# ICEBoard.net
KiCad netlist of a schematic drawn in Altium Designer
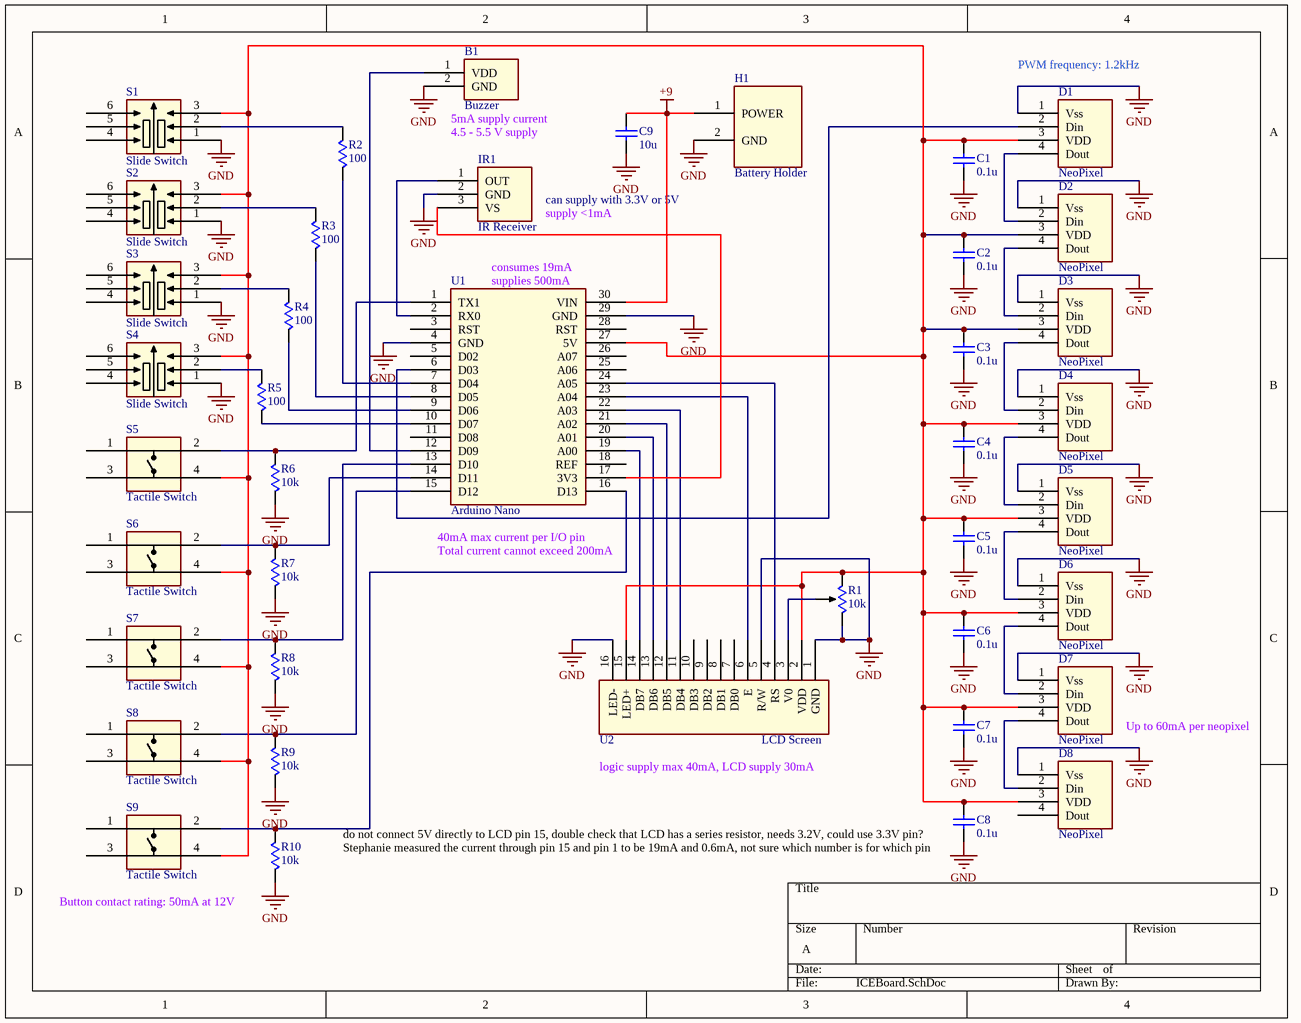
[diagram p0: ICEBoard.SchDoc]

(export (version "E")
  (design (tool "Eeschema 10.0.6"))
  (components
    (comp (ref "B1") (value "Buzzer") (footprint "TP124005") (libsource (lib "TP124005") (part "TP124005")))
    (comp (ref "C1") (value "0.1u") (footprint "Capacitor") (libsource (lib "Capacitor") (part "Capacitor")))
    (comp (ref "C2") (value "0.1u") (footprint "Capacitor") (libsource (lib "Capacitor") (part "Capacitor")))
    (comp (ref "C3") (value "0.1u") (footprint "Capacitor") (libsource (lib "Capacitor") (part "Capacitor")))
    (comp (ref "C4") (value "0.1u") (footprint "Capacitor") (libsource (lib "Capacitor") (part "Capacitor")))
    (comp (ref "C5") (value "0.1u") (footprint "Capacitor") (libsource (lib "Capacitor") (part "Capacitor")))
    (comp (ref "C6") (value "0.1u") (footprint "Capacitor") (libsource (lib "Capacitor") (part "Capacitor")))
    (comp (ref "C7") (value "0.1u") (footprint "Capacitor") (libsource (lib "Capacitor") (part "Capacitor")))
    (comp (ref "C8") (value "0.1u") (footprint "Capacitor") (libsource (lib "Capacitor") (part "Capacitor")))
    (comp (ref "C9")
      (value "10u")
      (footprint "PCBComponent_1")
      (libsource (lib "Capacitor") (part "Capacitor"))
    )
    (comp (ref "D1") (value "NeoPixel") (footprint "NeoPixel") (libsource (lib "NeoPixel") (part "NeoPixel")))
    (comp (ref "D2") (value "NeoPixel") (footprint "NeoPixel") (libsource (lib "NeoPixel") (part "NeoPixel")))
    (comp (ref "D3") (value "NeoPixel") (footprint "NeoPixel") (libsource (lib "NeoPixel") (part "NeoPixel")))
    (comp (ref "D4") (value "NeoPixel") (footprint "NeoPixel") (libsource (lib "NeoPixel") (part "NeoPixel")))
    (comp (ref "D5") (value "NeoPixel") (footprint "NeoPixel") (libsource (lib "NeoPixel") (part "NeoPixel")))
    (comp (ref "D6") (value "NeoPixel") (footprint "NeoPixel") (libsource (lib "NeoPixel") (part "NeoPixel")))
    (comp (ref "D7") (value "NeoPixel") (footprint "NeoPixel") (libsource (lib "NeoPixel") (part "NeoPixel")))
    (comp (ref "D8") (value "NeoPixel") (footprint "NeoPixel") (libsource (lib "NeoPixel") (part "NeoPixel")))
    (comp (ref "H1") (value "Battery Holder") (footprint "BH9VPC") (libsource (lib "BH9VPC") (part "BH9VPC")))
    (comp (ref "IR1")
      (value "IR Receiver")
      (footprint "TSOP382")
      (libsource (lib "TSOP382") (part "TSOP382"))
    )
    (comp (ref "R1")
      (value "10k")
      (footprint "TC33X")
      (libsource (lib "Resistor - Variable") (part "Resistor - Variable"))
    )
    (comp (ref "R2") (value "100") (footprint "Resistor1608") (libsource (lib "Resistor") (part "Resistor")))
    (comp (ref "R3") (value "100") (footprint "Resistor1608") (libsource (lib "Resistor") (part "Resistor")))
    (comp (ref "R4") (value "100") (footprint "Resistor1608") (libsource (lib "Resistor") (part "Resistor")))
    (comp (ref "R5") (value "100") (footprint "Resistor1608") (libsource (lib "Resistor") (part "Resistor")))
    (comp (ref "R6") (value "10k") (footprint "Resistor1608") (libsource (lib "Resistor") (part "Resistor")))
    (comp (ref "R7") (value "10k") (footprint "Resistor1608") (libsource (lib "Resistor") (part "Resistor")))
    (comp (ref "R8") (value "10k") (footprint "Resistor1608") (libsource (lib "Resistor") (part "Resistor")))
    (comp (ref "R9") (value "10k") (footprint "Resistor1608") (libsource (lib "Resistor") (part "Resistor")))
    (comp (ref "R10") (value "10k") (footprint "Resistor1608") (libsource (lib "Resistor") (part "Resistor")))
    (comp (ref "S1")
      (value "Slide Switch")
      (footprint "JS202011SCQN")
      (libsource (lib "JS202011SCQN") (part "JS202011SCQN"))
    )
    (comp (ref "S2")
      (value "Slide Switch")
      (footprint "JS202011SCQN")
      (libsource (lib "JS202011SCQN") (part "JS202011SCQN"))
    )
    (comp (ref "S3")
      (value "Slide Switch")
      (footprint "JS202011SCQN")
      (libsource (lib "JS202011SCQN") (part "JS202011SCQN"))
    )
    (comp (ref "S4")
      (value "Slide Switch")
      (footprint "JS202011SCQN")
      (libsource (lib "JS202011SCQN") (part "JS202011SCQN"))
    )
    (comp (ref "S5") (value "Tactile Switch") (footprint "PTS645") (libsource (lib "PTS645") (part "PTS645")))
    (comp (ref "S6") (value "Tactile Switch") (footprint "PTS645") (libsource (lib "PTS645") (part "PTS645")))
    (comp (ref "S7") (value "Tactile Switch") (footprint "PTS645") (libsource (lib "PTS645") (part "PTS645")))
    (comp (ref "S8") (value "Tactile Switch") (footprint "PTS645") (libsource (lib "PTS645") (part "PTS645")))
    (comp (ref "S9") (value "Tactile Switch") (footprint "PTS645") (libsource (lib "PTS645") (part "PTS645")))
    (comp (ref "U1")
      (value "Arduino Nano")
      (footprint "ArduinoNano")
      (libsource (lib "ArduinoNano") (part "ArduinoNano"))
    )
    (comp (ref "U2")
      (value "LCD Screen")
      (footprint "TC1602A-01T")
      (libsource (lib "TC1602A-01T") (part "TC1602A-01T"))
    )
  )
  (nets
    (net (code "1") (name "+9") (class "Default")
      (node (ref "C9") (pin "1") (pinfunction "1_1") (pintype "passive"))
      (node (ref "H1") (pin "1") (pinfunction "POWER_1") (pintype "passive"))
      (node (ref "U1") (pin "30") (pinfunction "VIN_30") (pintype "passive"))
    )
    (net (code "2") (name "GND") (class "Default")
      (node (ref "B1") (pin "2") (pinfunction "GND_2") (pintype "passive"))
      (node (ref "C1") (pin "2") (pinfunction "2_2") (pintype "passive"))
      (node (ref "C2") (pin "2") (pinfunction "2_2") (pintype "passive"))
      (node (ref "C3") (pin "2") (pinfunction "2_2") (pintype "passive"))
      (node (ref "C4") (pin "2") (pinfunction "2_2") (pintype "passive"))
      (node (ref "C5") (pin "2") (pinfunction "2_2") (pintype "passive"))
      (node (ref "C6") (pin "2") (pinfunction "2_2") (pintype "passive"))
      (node (ref "C7") (pin "2") (pinfunction "2_2") (pintype "passive"))
      (node (ref "C8") (pin "2") (pinfunction "2_2") (pintype "passive"))
      (node (ref "C9") (pin "2") (pinfunction "2_2") (pintype "passive"))
      (node (ref "D1") (pin "1") (pinfunction "Vss_1") (pintype "passive"))
      (node (ref "D2") (pin "1") (pinfunction "Vss_1") (pintype "passive"))
      (node (ref "D3") (pin "1") (pinfunction "Vss_1") (pintype "passive"))
      (node (ref "D4") (pin "1") (pinfunction "Vss_1") (pintype "passive"))
      (node (ref "D5") (pin "1") (pinfunction "Vss_1") (pintype "passive"))
      (node (ref "D6") (pin "1") (pinfunction "Vss_1") (pintype "passive"))
      (node (ref "D7") (pin "1") (pinfunction "Vss_1") (pintype "passive"))
      (node (ref "D8") (pin "1") (pinfunction "Vss_1") (pintype "passive"))
      (node (ref "H1") (pin "2") (pinfunction "GND_2") (pintype "passive"))
      (node (ref "IR1") (pin "2") (pinfunction "GND_2") (pintype "passive"))
      (node (ref "R1") (pin "1") (pinfunction "1_1") (pintype "passive"))
      (node (ref "R10") (pin "1") (pinfunction "1_1") (pintype "passive"))
      (node (ref "R6") (pin "1") (pinfunction "1_1") (pintype "passive"))
      (node (ref "R7") (pin "1") (pinfunction "1_1") (pintype "passive"))
      (node (ref "R8") (pin "1") (pinfunction "1_1") (pintype "passive"))
      (node (ref "R9") (pin "1") (pinfunction "1_1") (pintype "passive"))
      (node (ref "S1") (pin "1") (pintype "passive"))
      (node (ref "S2") (pin "1") (pintype "passive"))
      (node (ref "S3") (pin "1") (pintype "passive"))
      (node (ref "S4") (pin "1") (pintype "passive"))
      (node (ref "U1") (pin "29") (pinfunction "GND_29") (pintype "passive"))
      (node (ref "U1") (pin "4") (pinfunction "GND_4") (pintype "passive"))
      (node (ref "U2") (pin "1") (pinfunction "GND_1") (pintype "passive"))
      (node (ref "U2") (pin "16") (pinfunction "LED-_16") (pintype "passive"))
      (node (ref "U2") (pin "5") (pinfunction "R/W_5") (pintype "passive"))
    )
    (net (code "3") (name "Net-(B1-VDD)") (class "Default")
      (node (ref "B1") (pin "1") (pinfunction "VDD_1") (pintype "passive"))
      (node (ref "U1") (pin "12") (pinfunction "D09_12") (pintype "passive"))
    )
    (net (code "4") (name "Net-(D1-Din)") (class "Default")
      (node (ref "D1") (pin "2") (pinfunction "Din_2") (pintype "passive"))
      (node (ref "U1") (pin "6") (pinfunction "D03_6") (pintype "passive"))
    )
    (net (code "5") (name "Net-(D1-Dout)") (class "Default")
      (node (ref "D1") (pin "4") (pinfunction "Dout_4") (pintype "passive"))
      (node (ref "D2") (pin "2") (pinfunction "Din_2") (pintype "passive"))
    )
    (net (code "6") (name "Net-(D1-VDD)") (class "Default")
      (node (ref "C1") (pin "1") (pinfunction "1_1") (pintype "passive"))
      (node (ref "C2") (pin "1") (pinfunction "1_1") (pintype "passive"))
      (node (ref "C3") (pin "1") (pinfunction "1_1") (pintype "passive"))
      (node (ref "C4") (pin "1") (pinfunction "1_1") (pintype "passive"))
      (node (ref "C5") (pin "1") (pinfunction "1_1") (pintype "passive"))
      (node (ref "C6") (pin "1") (pinfunction "1_1") (pintype "passive"))
      (node (ref "C7") (pin "1") (pinfunction "1_1") (pintype "passive"))
      (node (ref "C8") (pin "1") (pinfunction "1_1") (pintype "passive"))
      (node (ref "D1") (pin "3") (pinfunction "VDD_3") (pintype "passive"))
      (node (ref "D2") (pin "3") (pinfunction "VDD_3") (pintype "passive"))
      (node (ref "D3") (pin "3") (pinfunction "VDD_3") (pintype "passive"))
      (node (ref "D4") (pin "3") (pinfunction "VDD_3") (pintype "passive"))
      (node (ref "D5") (pin "3") (pinfunction "VDD_3") (pintype "passive"))
      (node (ref "D6") (pin "3") (pinfunction "VDD_3") (pintype "passive"))
      (node (ref "D7") (pin "3") (pinfunction "VDD_3") (pintype "passive"))
      (node (ref "D8") (pin "3") (pinfunction "VDD_3") (pintype "passive"))
      (node (ref "R1") (pin "3") (pinfunction "3_3") (pintype "passive"))
      (node (ref "S1") (pin "3") (pintype "passive"))
      (node (ref "S2") (pin "3") (pintype "passive"))
      (node (ref "S3") (pin "3") (pintype "passive"))
      (node (ref "S4") (pin "3") (pintype "passive"))
      (node (ref "S5") (pin "4") (pintype "passive"))
      (node (ref "S6") (pin "4") (pintype "passive"))
      (node (ref "S7") (pin "4") (pintype "passive"))
      (node (ref "S8") (pin "4") (pintype "passive"))
      (node (ref "S9") (pin "4") (pintype "passive"))
      (node (ref "U1") (pin "27") (pinfunction "5V_27") (pintype "passive"))
      (node (ref "U2") (pin "15") (pinfunction "LED+_15") (pintype "passive"))
      (node (ref "U2") (pin "2") (pinfunction "VDD_2") (pintype "passive"))
    )
    (net (code "7") (name "Net-(D2-Dout)") (class "Default")
      (node (ref "D2") (pin "4") (pinfunction "Dout_4") (pintype "passive"))
      (node (ref "D3") (pin "2") (pinfunction "Din_2") (pintype "passive"))
    )
    (net (code "8") (name "Net-(D3-Dout)") (class "Default")
      (node (ref "D3") (pin "4") (pinfunction "Dout_4") (pintype "passive"))
      (node (ref "D4") (pin "2") (pinfunction "Din_2") (pintype "passive"))
    )
    (net (code "9") (name "Net-(D4-Dout)") (class "Default")
      (node (ref "D4") (pin "4") (pinfunction "Dout_4") (pintype "passive"))
      (node (ref "D5") (pin "2") (pinfunction "Din_2") (pintype "passive"))
    )
    (net (code "10") (name "Net-(D5-Dout)") (class "Default")
      (node (ref "D5") (pin "4") (pinfunction "Dout_4") (pintype "passive"))
      (node (ref "D6") (pin "2") (pinfunction "Din_2") (pintype "passive"))
    )
    (net (code "11") (name "Net-(D6-Dout)") (class "Default")
      (node (ref "D6") (pin "4") (pinfunction "Dout_4") (pintype "passive"))
      (node (ref "D7") (pin "2") (pinfunction "Din_2") (pintype "passive"))
    )
    (net (code "12") (name "Net-(D7-Dout)") (class "Default")
      (node (ref "D7") (pin "4") (pinfunction "Dout_4") (pintype "passive"))
      (node (ref "D8") (pin "2") (pinfunction "Din_2") (pintype "passive"))
    )
    (net (code "13") (name "Net-(IR1-OUT)") (class "Default")
      (node (ref "IR1") (pin "1") (pinfunction "OUT_1") (pintype "passive"))
      (node (ref "U1") (pin "2") (pinfunction "RX0_2") (pintype "passive"))
    )
    (net (code "14") (name "Net-(IR1-VS)") (class "Default")
      (node (ref "IR1") (pin "3") (pinfunction "VS_3") (pintype "passive"))
      (node (ref "U1") (pin "17") (pinfunction "3V3_17") (pintype "passive"))
    )
    (net (code "15") (name "Net-(R2-Pad2)") (class "Default")
      (node (ref "R2") (pin "2") (pinfunction "2_2") (pintype "passive"))
      (node (ref "S1") (pin "2") (pintype "passive"))
    )
    (net (code "16") (name "Net-(R3-Pad2)") (class "Default")
      (node (ref "R3") (pin "2") (pinfunction "2_2") (pintype "passive"))
      (node (ref "S2") (pin "2") (pintype "passive"))
    )
    (net (code "17") (name "Net-(R4-Pad2)") (class "Default")
      (node (ref "R4") (pin "2") (pinfunction "2_2") (pintype "passive"))
      (node (ref "S3") (pin "2") (pintype "passive"))
    )
    (net (code "18") (name "Net-(R5-Pad2)") (class "Default")
      (node (ref "R5") (pin "2") (pinfunction "2_2") (pintype "passive"))
      (node (ref "S4") (pin "2") (pintype "passive"))
    )
    (net (code "19") (name "Net-(U1-A00)") (class "Default")
      (node (ref "U1") (pin "19") (pinfunction "A00_19") (pintype "passive"))
      (node (ref "U2") (pin "14") (pinfunction "DB7_14") (pintype "passive"))
    )
    (net (code "20") (name "Net-(U1-A01)") (class "Default")
      (node (ref "U1") (pin "20") (pinfunction "A01_20") (pintype "passive"))
      (node (ref "U2") (pin "13") (pinfunction "DB6_13") (pintype "passive"))
    )
    (net (code "21") (name "Net-(U1-A02)") (class "Default")
      (node (ref "U1") (pin "21") (pinfunction "A02_21") (pintype "passive"))
      (node (ref "U2") (pin "12") (pinfunction "DB5_12") (pintype "passive"))
    )
    (net (code "22") (name "Net-(U1-A03)") (class "Default")
      (node (ref "U1") (pin "22") (pinfunction "A03_22") (pintype "passive"))
      (node (ref "U2") (pin "11") (pinfunction "DB4_11") (pintype "passive"))
    )
    (net (code "23") (name "Net-(U1-A04)") (class "Default")
      (node (ref "U1") (pin "23") (pinfunction "A04_23") (pintype "passive"))
      (node (ref "U2") (pin "6") (pinfunction "E_6") (pintype "passive"))
    )
    (net (code "24") (name "Net-(U1-A05)") (class "Default")
      (node (ref "U1") (pin "24") (pinfunction "A05_24") (pintype "passive"))
      (node (ref "U2") (pin "4") (pinfunction "RS_4") (pintype "passive"))
    )
    (net (code "25") (name "Net-(U1-D04)") (class "Default")
      (node (ref "R2") (pin "1") (pinfunction "1_1") (pintype "passive"))
      (node (ref "U1") (pin "7") (pinfunction "D04_7") (pintype "passive"))
    )
    (net (code "26") (name "Net-(U1-D05)") (class "Default")
      (node (ref "R3") (pin "1") (pinfunction "1_1") (pintype "passive"))
      (node (ref "U1") (pin "8") (pinfunction "D05_8") (pintype "passive"))
    )
    (net (code "27") (name "Net-(U1-D06)") (class "Default")
      (node (ref "R4") (pin "1") (pinfunction "1_1") (pintype "passive"))
      (node (ref "U1") (pin "9") (pinfunction "D06_9") (pintype "passive"))
    )
    (net (code "28") (name "Net-(U1-D07)") (class "Default")
      (node (ref "R5") (pin "1") (pinfunction "1_1") (pintype "passive"))
      (node (ref "U1") (pin "10") (pinfunction "D07_10") (pintype "passive"))
    )
    (net (code "29") (name "Net-(U1-D10)") (class "Default")
      (node (ref "R8") (pin "2") (pinfunction "2_2") (pintype "passive"))
      (node (ref "S7") (pin "2") (pintype "passive"))
      (node (ref "U1") (pin "13") (pinfunction "D10_13") (pintype "passive"))
    )
    (net (code "30") (name "Net-(U1-D11)") (class "Default")
      (node (ref "R7") (pin "2") (pinfunction "2_2") (pintype "passive"))
      (node (ref "S6") (pin "2") (pintype "passive"))
      (node (ref "U1") (pin "14") (pinfunction "D11_14") (pintype "passive"))
    )
    (net (code "31") (name "Net-(U1-D12)") (class "Default")
      (node (ref "R9") (pin "2") (pinfunction "2_2") (pintype "passive"))
      (node (ref "S8") (pin "2") (pintype "passive"))
      (node (ref "U1") (pin "15") (pinfunction "D12_15") (pintype "passive"))
    )
    (net (code "32") (name "Net-(U1-D13)") (class "Default")
      (node (ref "R10") (pin "2") (pinfunction "2_2") (pintype "passive"))
      (node (ref "S9") (pin "2") (pintype "passive"))
      (node (ref "U1") (pin "16") (pinfunction "D13_16") (pintype "passive"))
    )
    (net (code "33") (name "Net-(U1-TX1)") (class "Default")
      (node (ref "R6") (pin "2") (pinfunction "2_2") (pintype "passive"))
      (node (ref "S5") (pin "2") (pintype "passive"))
      (node (ref "U1") (pin "1") (pinfunction "TX1_1") (pintype "passive"))
    )
    (net (code "34") (name "Net-(U2-V0)") (class "Default")
      (node (ref "R1") (pin "2") (pinfunction "2_2") (pintype "passive"))
      (node (ref "U2") (pin "3") (pinfunction "V0_3") (pintype "passive"))
    )
    (net (code "35") (name "unconnected-(D8-Dout-Pad4)") (class "Default")
      (node (ref "D8") (pin "4") (pinfunction "Dout_4") (pintype "passive"))
    )
    (net (code "36") (name "unconnected-(S1-Pad4)") (class "Default")
      (node (ref "S1") (pin "4") (pintype "passive"))
    )
    (net (code "37") (name "unconnected-(S1-Pad5)") (class "Default")
      (node (ref "S1") (pin "5") (pintype "passive"))
    )
    (net (code "38") (name "unconnected-(S1-Pad6)") (class "Default")
      (node (ref "S1") (pin "6") (pintype "passive"))
    )
    (net (code "39") (name "unconnected-(S2-Pad4)") (class "Default")
      (node (ref "S2") (pin "4") (pintype "passive"))
    )
    (net (code "40") (name "unconnected-(S2-Pad5)") (class "Default")
      (node (ref "S2") (pin "5") (pintype "passive"))
    )
    (net (code "41") (name "unconnected-(S2-Pad6)") (class "Default")
      (node (ref "S2") (pin "6") (pintype "passive"))
    )
    (net (code "42") (name "unconnected-(S3-Pad4)") (class "Default")
      (node (ref "S3") (pin "4") (pintype "passive"))
    )
    (net (code "43") (name "unconnected-(S3-Pad5)") (class "Default")
      (node (ref "S3") (pin "5") (pintype "passive"))
    )
    (net (code "44") (name "unconnected-(S3-Pad6)") (class "Default")
      (node (ref "S3") (pin "6") (pintype "passive"))
    )
    (net (code "45") (name "unconnected-(S4-Pad4)") (class "Default")
      (node (ref "S4") (pin "4") (pintype "passive"))
    )
    (net (code "46") (name "unconnected-(S4-Pad5)") (class "Default")
      (node (ref "S4") (pin "5") (pintype "passive"))
    )
    (net (code "47") (name "unconnected-(S4-Pad6)") (class "Default")
      (node (ref "S4") (pin "6") (pintype "passive"))
    )
    (net (code "48") (name "unconnected-(S5-Pad1)") (class "Default")
      (node (ref "S5") (pin "1") (pintype "passive"))
    )
    (net (code "49") (name "unconnected-(S5-Pad3)") (class "Default")
      (node (ref "S5") (pin "3") (pintype "passive"))
    )
    (net (code "50") (name "unconnected-(S6-Pad1)") (class "Default")
      (node (ref "S6") (pin "1") (pintype "passive"))
    )
    (net (code "51") (name "unconnected-(S6-Pad3)") (class "Default")
      (node (ref "S6") (pin "3") (pintype "passive"))
    )
    (net (code "52") (name "unconnected-(S7-Pad1)") (class "Default")
      (node (ref "S7") (pin "1") (pintype "passive"))
    )
    (net (code "53") (name "unconnected-(S7-Pad3)") (class "Default")
      (node (ref "S7") (pin "3") (pintype "passive"))
    )
    (net (code "54") (name "unconnected-(S8-Pad1)") (class "Default")
      (node (ref "S8") (pin "1") (pintype "passive"))
    )
    (net (code "55") (name "unconnected-(S8-Pad3)") (class "Default")
      (node (ref "S8") (pin "3") (pintype "passive"))
    )
    (net (code "56") (name "unconnected-(S9-Pad1)") (class "Default")
      (node (ref "S9") (pin "1") (pintype "passive"))
    )
    (net (code "57") (name "unconnected-(S9-Pad3)") (class "Default")
      (node (ref "S9") (pin "3") (pintype "passive"))
    )
    (net (code "58") (name "unconnected-(U1-A06-Pad25)") (class "Default")
      (node (ref "U1") (pin "25") (pinfunction "A06_25") (pintype "passive"))
    )
    (net (code "59") (name "unconnected-(U1-A07-Pad26)") (class "Default")
      (node (ref "U1") (pin "26") (pinfunction "A07_26") (pintype "passive"))
    )
    (net (code "60") (name "unconnected-(U1-D02-Pad5)") (class "Default")
      (node (ref "U1") (pin "5") (pinfunction "D02_5") (pintype "passive"))
    )
    (net (code "61") (name "unconnected-(U1-D08-Pad11)") (class "Default")
      (node (ref "U1") (pin "11") (pinfunction "D08_11") (pintype "passive"))
    )
    (net (code "62") (name "unconnected-(U1-REF-Pad18)") (class "Default")
      (node (ref "U1") (pin "18") (pinfunction "REF_18") (pintype "passive"))
    )
    (net (code "63") (name "unconnected-(U1-RST-Pad3)") (class "Default")
      (node (ref "U1") (pin "3") (pinfunction "RST_3") (pintype "passive"))
    )
    (net (code "64") (name "unconnected-(U1-RST-Pad28)") (class "Default")
      (node (ref "U1") (pin "28") (pinfunction "RST_28") (pintype "passive"))
    )
    (net (code "65") (name "unconnected-(U2-DB0-Pad7)") (class "Default")
      (node (ref "U2") (pin "7") (pinfunction "DB0_7") (pintype "passive"))
    )
    (net (code "66") (name "unconnected-(U2-DB1-Pad8)") (class "Default")
      (node (ref "U2") (pin "8") (pinfunction "DB1_8") (pintype "passive"))
    )
    (net (code "67") (name "unconnected-(U2-DB2-Pad9)") (class "Default")
      (node (ref "U2") (pin "9") (pinfunction "DB2_9") (pintype "passive"))
    )
    (net (code "68") (name "unconnected-(U2-DB3-Pad10)") (class "Default")
      (node (ref "U2") (pin "10") (pinfunction "DB3_10") (pintype "passive"))
    )
  )
)
